# YuriPre.net
KiCad netlist of a schematic drawn in EasyEDA Pro
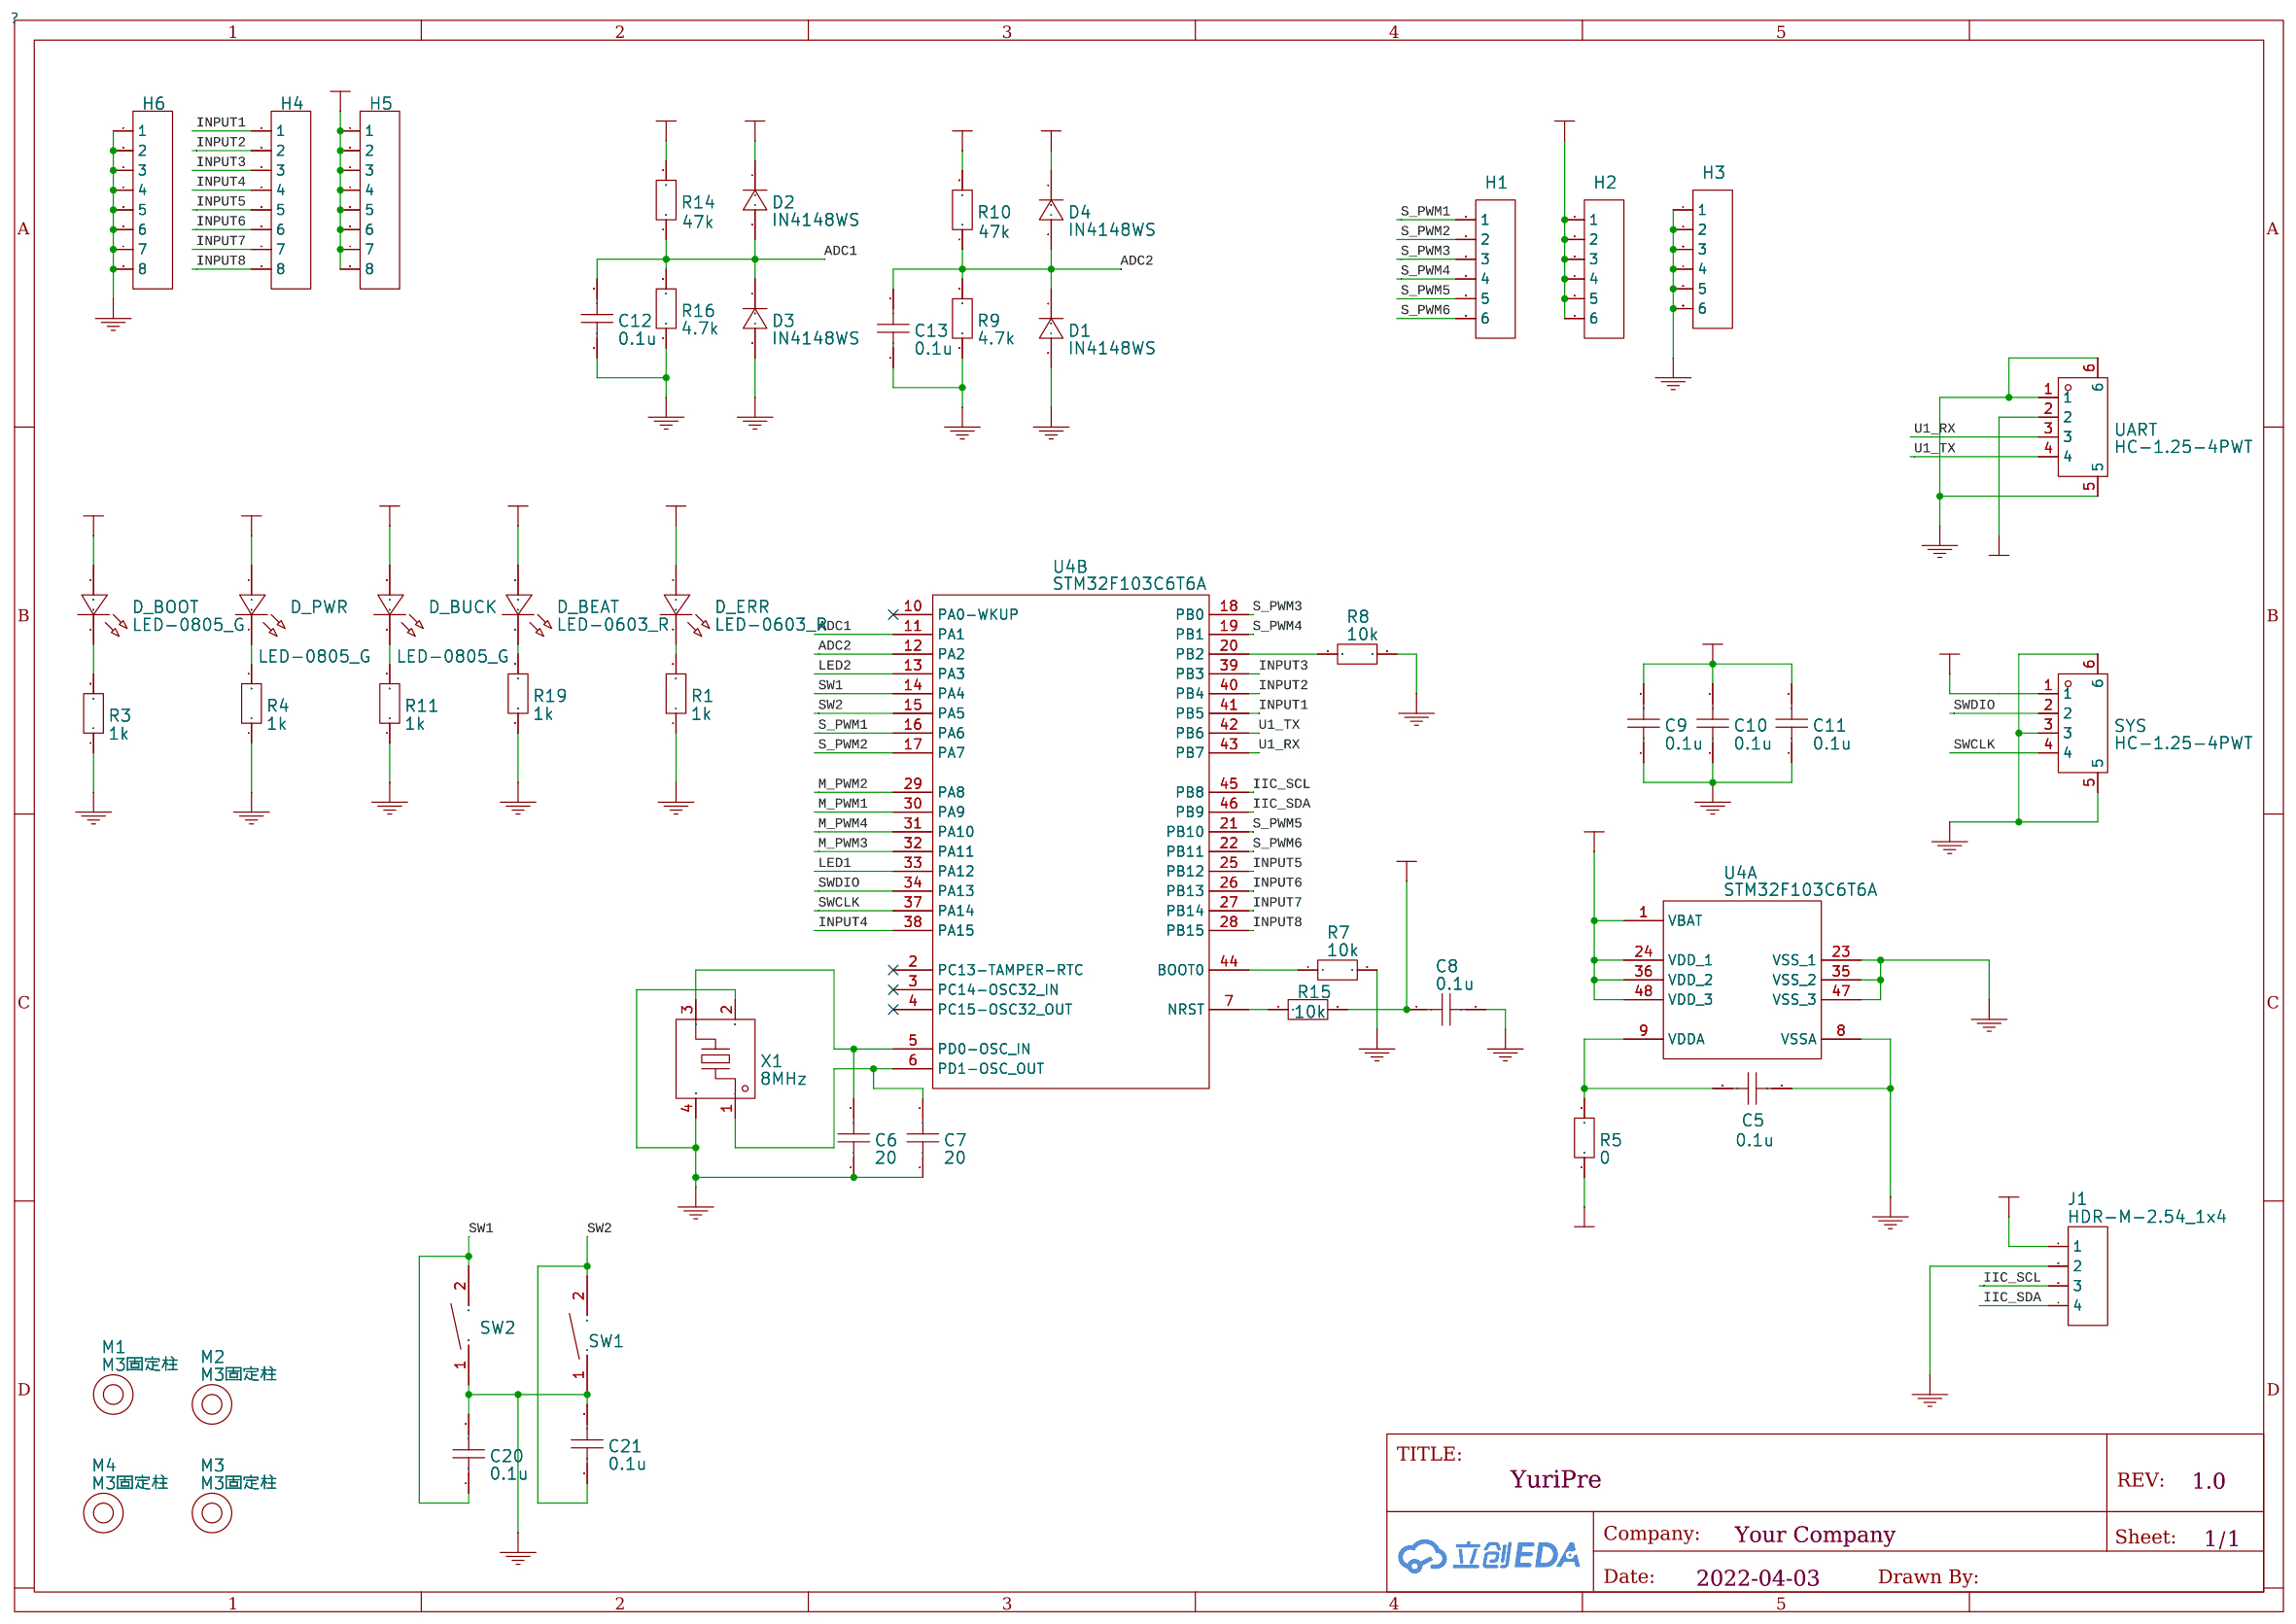
[diagram p0: MAIN_PART]
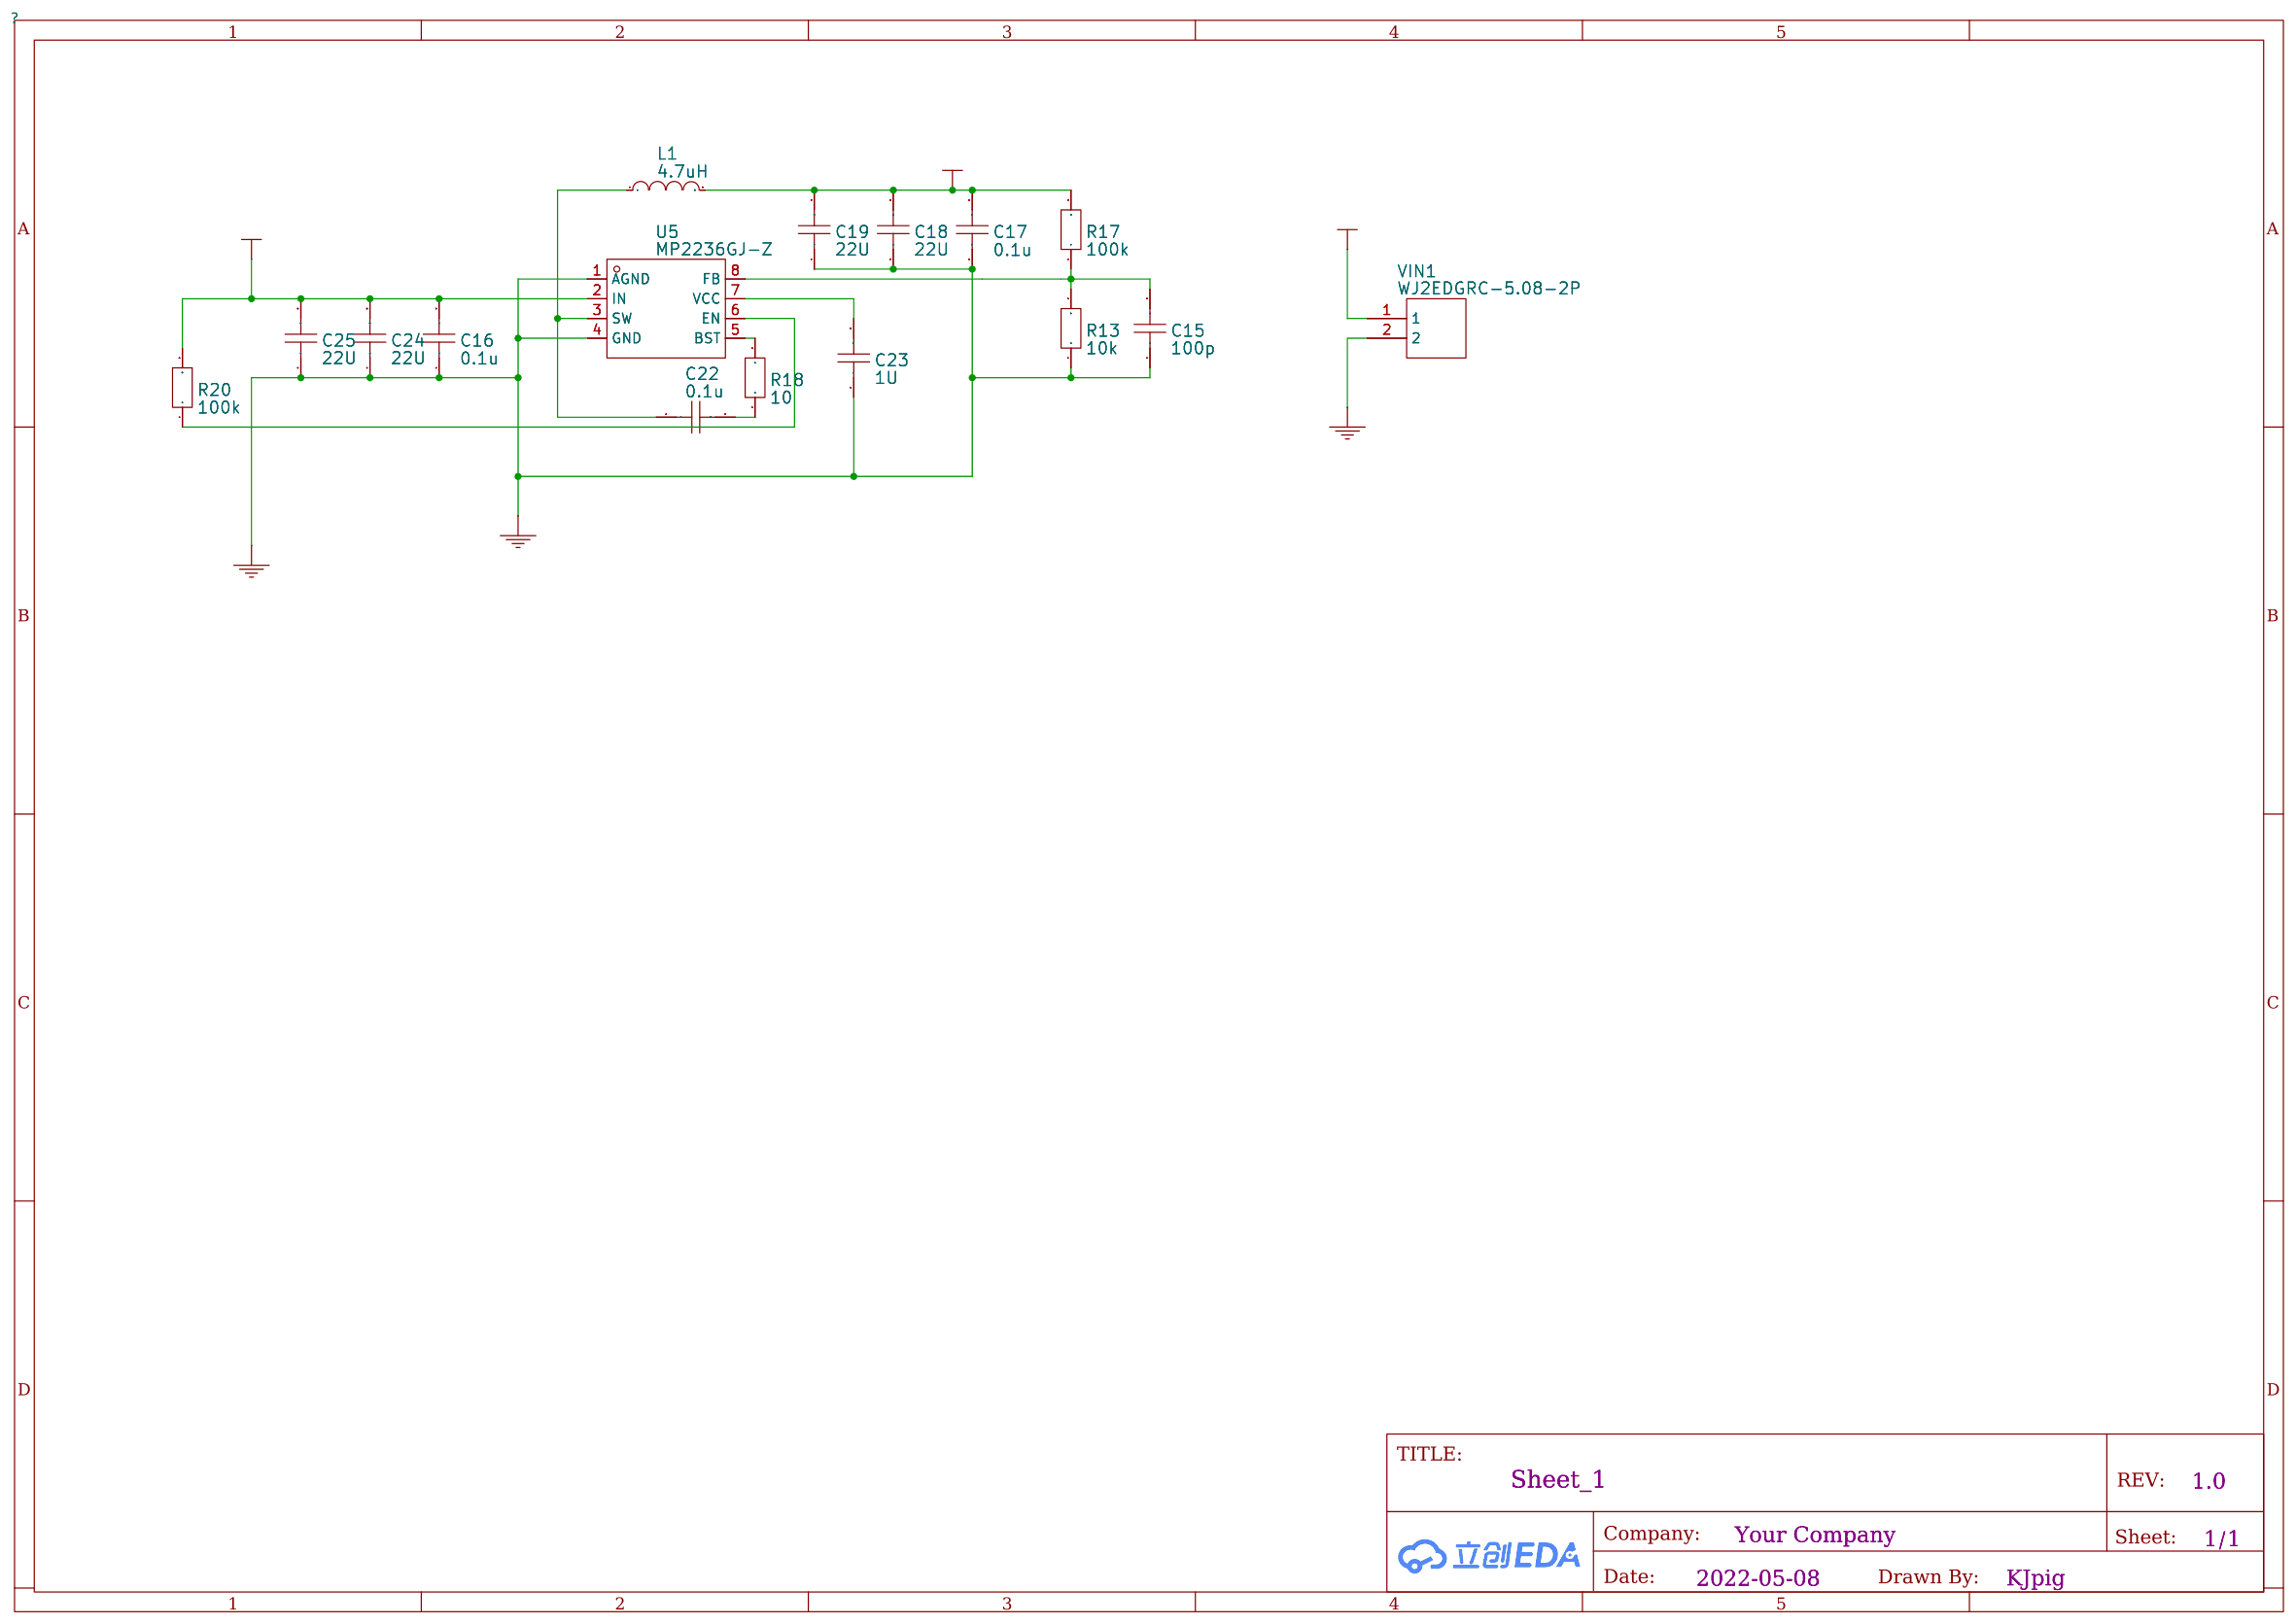
[diagram p1: PWR_PART]
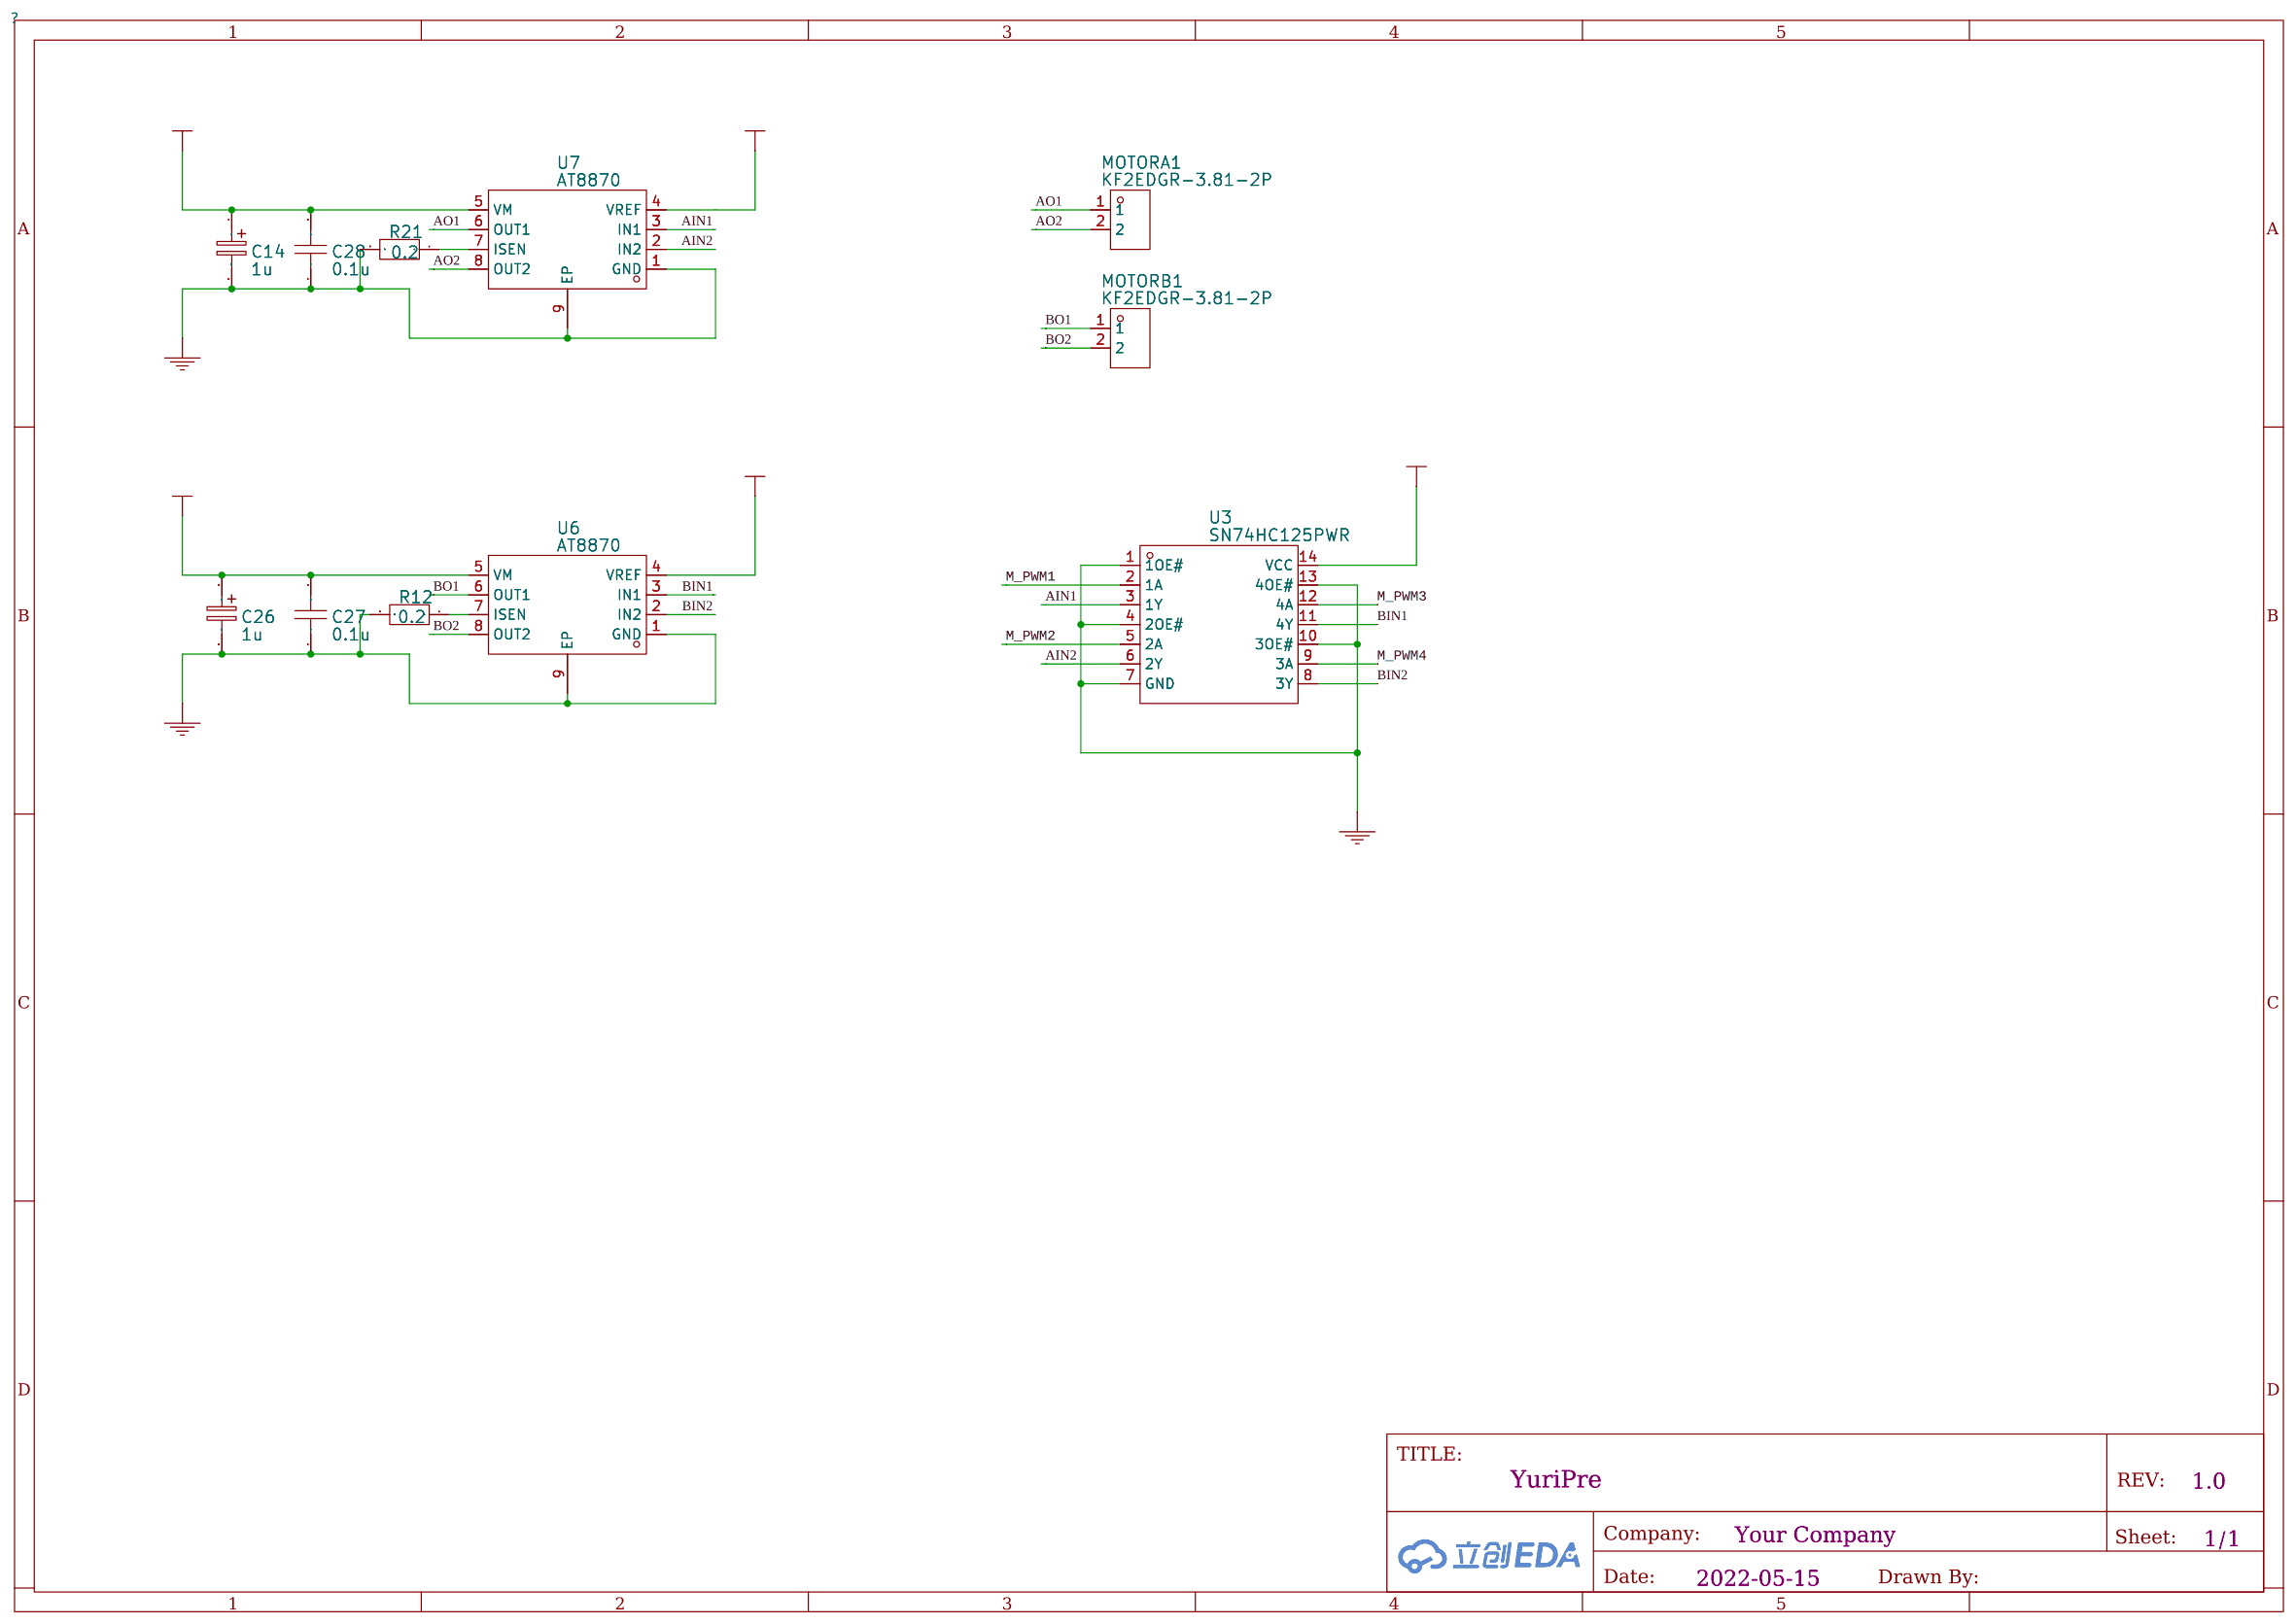
[diagram p2: MOTOR_PART]

(export (version "E")
  (design (tool "Eeschema 10.0.6"))
  (components
    (comp (ref "C5")
      (value "0.1u")
      (footprint "easyedapro:C0603")
      (libsource (lib "easyedapro") (part "0.1u"))
    )
    (comp (ref "C6") (value "20") (footprint "easyedapro:C0603") (libsource (lib "easyedapro") (part "20")))
    (comp (ref "C7") (value "20") (footprint "easyedapro:C0603") (libsource (lib "easyedapro") (part "20")))
    (comp (ref "C8")
      (value "0.1u")
      (footprint "easyedapro:C0603")
      (libsource (lib "easyedapro") (part "0.1u"))
    )
    (comp (ref "C9")
      (value "0.1u")
      (footprint "easyedapro:C0603")
      (libsource (lib "easyedapro") (part "0.1u"))
    )
    (comp (ref "C10")
      (value "0.1u")
      (footprint "easyedapro:C0603")
      (libsource (lib "easyedapro") (part "0.1u"))
    )
    (comp (ref "C11")
      (value "0.1u")
      (footprint "easyedapro:C0603")
      (libsource (lib "easyedapro") (part "0.1u"))
    )
    (comp (ref "C12")
      (value "0.1u")
      (footprint "easyedapro:C0603")
      (libsource (lib "easyedapro") (part "0.1u"))
    )
    (comp (ref "C13")
      (value "0.1u")
      (footprint "easyedapro:C0603")
      (libsource (lib "easyedapro") (part "0.1u"))
    )
    (comp (ref "C20")
      (value "0.1u")
      (footprint "easyedapro:C0603")
      (libsource (lib "easyedapro") (part "0.1u"))
    )
    (comp (ref "C21")
      (value "0.1u")
      (footprint "easyedapro:C0603")
      (libsource (lib "easyedapro") (part "0.1u"))
    )
    (comp (ref "D1")
      (value "IN4148WS")
      (footprint "easyedapro:SOD-323_L1.8-W1.3-LS2.5-RD")
      (fields (field (name "Manufacturer") "Leshan Radio"))
      (libsource (lib "easyedapro") (part "IN4148WS"))
    )
    (comp (ref "D2")
      (value "IN4148WS")
      (footprint "easyedapro:SOD-323_L1.8-W1.3-LS2.5-RD")
      (fields (field (name "Manufacturer") "Leshan Radio"))
      (libsource (lib "easyedapro") (part "IN4148WS"))
    )
    (comp (ref "D3")
      (value "IN4148WS")
      (footprint "easyedapro:SOD-323_L1.8-W1.3-LS2.5-RD")
      (fields (field (name "Manufacturer") "Leshan Radio"))
      (libsource (lib "easyedapro") (part "IN4148WS"))
    )
    (comp (ref "D4")
      (value "IN4148WS")
      (footprint "easyedapro:SOD-323_L1.8-W1.3-LS2.5-RD")
      (fields (field (name "Manufacturer") "Leshan Radio"))
      (libsource (lib "easyedapro") (part "IN4148WS"))
    )
    (comp (ref "D_BEAT")
      (value "LED-0603_R")
      (footprint "easyedapro:LED0603_RED")
      (fields
        (field (name "Manufacturer Part") "19-217/R6C-AL1M2VY/3T")
        (field (name "Manufacturer") "EVERLIGHT(台湾亿光)")
      )
      (libsource (lib "easyedapro") (part "LED-0603_R"))
    )
    (comp (ref "D_BOOT")
      (value "LED-0805_G")
      (footprint "easyedapro:LED0805_GREEN")
      (fields (field (name "Manufacturer Part") "NCD0805G1") (field (name "Manufacturer") "国星光电"))
      (libsource (lib "easyedapro") (part "LED-0805_G"))
    )
    (comp (ref "D_BUCK")
      (value "LED-0805_G")
      (footprint "easyedapro:LED0805_GREEN")
      (fields (field (name "Manufacturer Part") "NCD0805G1") (field (name "Manufacturer") "国星光电"))
      (libsource (lib "easyedapro") (part "LED-0805_G"))
    )
    (comp (ref "D_ERR")
      (value "LED-0603_R")
      (footprint "easyedapro:LED0603_RED")
      (fields
        (field (name "Manufacturer Part") "19-217/R6C-AL1M2VY/3T")
        (field (name "Manufacturer") "EVERLIGHT(台湾亿光)")
      )
      (libsource (lib "easyedapro") (part "LED-0603_R"))
    )
    (comp (ref "D_PWR")
      (value "LED-0805_G")
      (footprint "easyedapro:LED0805_GREEN")
      (fields (field (name "Manufacturer Part") "NCD0805G1") (field (name "Manufacturer") "国星光电"))
      (libsource (lib "easyedapro") (part "LED-0805_G"))
    )
    (comp (ref "H1")
      (value "HDR-F-2.54_1x6")
      (footprint "easyedapro:HDR-F-2.54_1X6")
      (libsource (lib "easyedapro") (part "HDR-F-2.54_1x6"))
    )
    (comp (ref "H2")
      (value "HDR-F-2.54_1x6")
      (footprint "easyedapro:HDR-F-2.54_1X6")
      (libsource (lib "easyedapro") (part "HDR-F-2.54_1x6"))
    )
    (comp (ref "H3")
      (value "HDR-F-2.54_1x6")
      (footprint "easyedapro:HDR-F-2.54_1X6")
      (libsource (lib "easyedapro") (part "HDR-F-2.54_1x6"))
    )
    (comp (ref "H4")
      (value "HDR-F-2.54_1x8")
      (footprint "easyedapro:HDR-F-2.54_1X8")
      (libsource (lib "easyedapro") (part "HDR-F-2.54_1x8"))
    )
    (comp (ref "H5")
      (value "HDR-F-2.54_1x8")
      (footprint "easyedapro:HDR-F-2.54_1X8")
      (libsource (lib "easyedapro") (part "HDR-F-2.54_1x8"))
    )
    (comp (ref "H6")
      (value "HDR-F-2.54_1x8")
      (footprint "easyedapro:HDR-F-2.54_1X8")
      (libsource (lib "easyedapro") (part "HDR-F-2.54_1x8"))
    )
    (comp (ref "J1")
      (value "HDR-M-2.54_1x4")
      (footprint "easyedapro:HDR-M-2.54_1X4")
      (libsource (lib "easyedapro") (part "HDR-M-2.54_1x4"))
    )
    (comp (ref "M1")
      (value "M3固定柱")
      (footprint "easyedapro:M3螺丝孔外直径6MM-带8小孔")
      (libsource (lib "easyedapro") (part "M3固定柱"))
    )
    (comp (ref "M2")
      (value "M3固定柱")
      (footprint "easyedapro:M3螺丝孔外直径6MM-带8小孔")
      (libsource (lib "easyedapro") (part "M3固定柱"))
    )
    (comp (ref "M3")
      (value "M3固定柱")
      (footprint "easyedapro:M3螺丝孔外直径6MM-带8小孔")
      (libsource (lib "easyedapro") (part "M3固定柱"))
    )
    (comp (ref "M4")
      (value "M3固定柱")
      (footprint "easyedapro:M3螺丝孔外直径6MM-带8小孔")
      (libsource (lib "easyedapro") (part "M3固定柱"))
    )
    (comp (ref "R1") (value "1k") (footprint "easyedapro:R0603") (libsource (lib "easyedapro") (part "1k")))
    (comp (ref "R3") (value "1k") (footprint "easyedapro:R0603") (libsource (lib "easyedapro") (part "1k")))
    (comp (ref "R4") (value "1k") (footprint "easyedapro:R0603") (libsource (lib "easyedapro") (part "1k")))
    (comp (ref "R5") (value "0") (footprint "easyedapro:R0603") (libsource (lib "easyedapro") (part "0_")))
    (comp (ref "R7") (value "10k") (footprint "easyedapro:R0603") (libsource (lib "easyedapro") (part "10k")))
    (comp (ref "R8") (value "10k") (footprint "easyedapro:R0603") (libsource (lib "easyedapro") (part "10k")))
    (comp (ref "R9")
      (value "4.7k")
      (footprint "easyedapro:R0603")
      (libsource (lib "easyedapro") (part "4.7k"))
    )
    (comp (ref "R10")
      (value "47k")
      (footprint "easyedapro:R0603")
      (libsource (lib "easyedapro") (part "47k"))
    )
    (comp (ref "R11") (value "1k") (footprint "easyedapro:R0603") (libsource (lib "easyedapro") (part "1k")))
    (comp (ref "R14")
      (value "47k")
      (footprint "easyedapro:R0603")
      (libsource (lib "easyedapro") (part "47k"))
    )
    (comp (ref "R15")
      (value "10k")
      (footprint "easyedapro:R0603")
      (libsource (lib "easyedapro") (part "10k"))
    )
    (comp (ref "R16")
      (value "4.7k")
      (footprint "easyedapro:R0603")
      (libsource (lib "easyedapro") (part "4.7k"))
    )
    (comp (ref "R19") (value "1k") (footprint "easyedapro:R0603") (libsource (lib "easyedapro") (part "1k")))
    (comp (ref "SW1")
      (value "TSA343G00D-250J2")
      (footprint "easyedapro:SW-SMD_L4.0-W2.9-P4.15-EH")
      (fields (field (name "Manufacturer") "BRIGHT"))
      (libsource (lib "easyedapro") (part "TSA343G00D-250J2"))
    )
    (comp (ref "SW2")
      (value "TSA343G00D-250J2")
      (footprint "easyedapro:SW-SMD_L4.0-W2.9-P4.15-EH")
      (fields (field (name "Manufacturer") "BRIGHT"))
      (libsource (lib "easyedapro") (part "TSA343G00D-250J2"))
    )
    (comp (ref "SYS")
      (value "HC-1.25-4PWT")
      (footprint "easyedapro:CONN-SMD_4P-P1.25-HC-1.25-4PWT")
      (fields (field (name "Manufacturer") "HCTL(华灿天禄)"))
      (libsource (lib "easyedapro") (part "HC-1.25-4PWT"))
    )
    (comp (ref "U4")
      (value "STM32F103C6T6A")
      (footprint "easyedapro:LQFP-48_L7.0-W7.0-P0.50-LS9.0-BL")
      (fields (field (name "Manufacturer") "ST"))
      (libsource (lib "easyedapro") (part "STM32F103C6T6A"))
    )
    (comp (ref "UART")
      (value "HC-1.25-4PWT")
      (footprint "easyedapro:CONN-SMD_4P-P1.25-HC-1.25-4PWT")
      (fields (field (name "Manufacturer") "HCTL(华灿天禄)"))
      (libsource (lib "easyedapro") (part "HC-1.25-4PWT"))
    )
    (comp (ref "X1")
      (value "8MHz")
      (footprint "easyedapro:CRYSTAL-SMD_4P-L3.2-W2.5-BL")
      (fields (field (name "Manufacturer Part") "X32258MSB4SI") (field (name "Manufacturer") "YXC扬兴科技"))
      (libsource (lib "easyedapro") (part "8MHz"))
    )
    (comp (ref "C15")
      (value "100p")
      (footprint "easyedapro:C0603")
      (libsource (lib "easyedapro") (part "100p"))
    )
    (comp (ref "C16")
      (value "0.1u")
      (footprint "easyedapro:C0603")
      (libsource (lib "easyedapro") (part "0.1u"))
    )
    (comp (ref "C17")
      (value "0.1u")
      (footprint "easyedapro:C0603")
      (libsource (lib "easyedapro") (part "0.1u"))
    )
    (comp (ref "C18")
      (value "22U")
      (footprint "easyedapro:C0805")
      (libsource (lib "easyedapro") (part "22U"))
    )
    (comp (ref "C19")
      (value "22U")
      (footprint "easyedapro:C0805")
      (libsource (lib "easyedapro") (part "22U"))
    )
    (comp (ref "C22")
      (value "0.1u")
      (footprint "easyedapro:C0603")
      (libsource (lib "easyedapro") (part "0.1u"))
    )
    (comp (ref "C23") (value "1U") (footprint "easyedapro:C0603") (libsource (lib "easyedapro") (part "1U")))
    (comp (ref "C24")
      (value "22U")
      (footprint "easyedapro:C0805")
      (libsource (lib "easyedapro") (part "22U"))
    )
    (comp (ref "C25")
      (value "22U")
      (footprint "easyedapro:C0805")
      (libsource (lib "easyedapro") (part "22U"))
    )
    (comp (ref "L1")
      (value "4.7uH")
      (footprint "easyedapro:IND-SMD_L7.1-W6.5")
      (fields (field (name "Manufacturer Part") "SPM6530T-4R7M") (field (name "Manufacturer") "TDK"))
      (libsource (lib "easyedapro") (part "4.7uH"))
    )
    (comp (ref "R13")
      (value "10k")
      (footprint "easyedapro:R0603")
      (libsource (lib "easyedapro") (part "10k"))
    )
    (comp (ref "R17")
      (value "100k")
      (footprint "easyedapro:R0603")
      (libsource (lib "easyedapro") (part "100k"))
    )
    (comp (ref "R18") (value "10") (footprint "easyedapro:R0603") (libsource (lib "easyedapro") (part "10")))
    (comp (ref "R20")
      (value "100k")
      (footprint "easyedapro:R0603")
      (libsource (lib "easyedapro") (part "100k"))
    )
    (comp (ref "U5")
      (value "MP2236GJ-Z")
      (footprint "easyedapro:TSOT-23-8_L2.9-W1.6-P0.65-LS2.8-BL")
      (libsource (lib "easyedapro") (part "MP2236GJ-Z"))
    )
    (comp (ref "VIN1")
      (value "WJ2EDGRC-5.08-2P")
      (footprint "easyedapro:CONN-TH_2P-P5.08_WJ2EDGRC-5.08-2P")
      (fields (field (name "Manufacturer") "ReliaPro"))
      (libsource (lib "easyedapro") (part "WJ2EDGRC-5.08-2P"))
    )
    (comp (ref "C14")
      (value "1u")
      (footprint "easyedapro:CAP-D6.3×H5.5")
      (libsource (lib "easyedapro") (part "1u"))
    )
    (comp (ref "C26")
      (value "1u")
      (footprint "easyedapro:CAP-D6.3×H5.5")
      (libsource (lib "easyedapro") (part "1u"))
    )
    (comp (ref "C27")
      (value "0.1u")
      (footprint "easyedapro:C0603")
      (libsource (lib "easyedapro") (part "0.1u"))
    )
    (comp (ref "C28")
      (value "0.1u")
      (footprint "easyedapro:C0603")
      (libsource (lib "easyedapro") (part "0.1u"))
    )
    (comp (ref "MOTORA1")
      (value "KF2EDGR-3.81-2P")
      (footprint "easyedapro:CONN-TH_2P-P3.81_KF2EDGR-3.81-2P")
      (fields (field (name "Manufacturer") "Cixi Kefa Elec"))
      (libsource (lib "easyedapro") (part "KF2EDGR-3.81-2P"))
    )
    (comp (ref "MOTORB1")
      (value "KF2EDGR-3.81-2P")
      (footprint "easyedapro:CONN-TH_2P-P3.81_KF2EDGR-3.81-2P")
      (fields (field (name "Manufacturer") "Cixi Kefa Elec"))
      (libsource (lib "easyedapro") (part "KF2EDGR-3.81-2P"))
    )
    (comp (ref "R12")
      (value "0.2")
      (footprint "easyedapro:R0603")
      (libsource (lib "easyedapro") (part "0.2"))
    )
    (comp (ref "R21")
      (value "0.2")
      (footprint "easyedapro:R0603")
      (libsource (lib "easyedapro") (part "0.2"))
    )
    (comp (ref "U3")
      (value "SN74HC125PWR")
      (footprint "easyedapro:TSSOP-14_L5.0-W4.4-P0.65-LS6.5-BL")
      (fields (field (name "Manufacturer") "Texas Instruments"))
      (libsource (lib "easyedapro") (part "SN74HC125PWR"))
    )
    (comp (ref "U6")
      (value "AT8870")
      (footprint "easyedapro:SOP-8_L4.9-W3.9-P1.27-LS6.0-BL-EP")
      (fields (field (name "Manufacturer") "Jiaxing Heroic Elec Tech"))
      (libsource (lib "easyedapro") (part "AT8870"))
    )
    (comp (ref "U7")
      (value "AT8870")
      (footprint "easyedapro:SOP-8_L4.9-W3.9-P1.27-LS6.0-BL-EP")
      (fields (field (name "Manufacturer") "Jiaxing Heroic Elec Tech"))
      (libsource (lib "easyedapro") (part "AT8870"))
    )
  )
  (nets
    (net (code "1") (name "+6.8V") (class "Default")
      (node (ref "C17") (pin "2") (pinfunction "2_2") (pintype "input"))
      (node (ref "C18") (pin "2") (pinfunction "2_2") (pintype "input"))
      (node (ref "C19") (pin "2") (pinfunction "2_2") (pintype "input"))
      (node (ref "D_BUCK") (pin "1") (pinfunction "1_1") (pintype "input"))
      (node (ref "H2") (pin "1") (pinfunction "1_1") (pintype "input"))
      (node (ref "H2") (pin "2") (pinfunction "2_2") (pintype "input"))
      (node (ref "H2") (pin "3") (pinfunction "3_3") (pintype "input"))
      (node (ref "H2") (pin "4") (pinfunction "4_4") (pintype "input"))
      (node (ref "H2") (pin "5") (pinfunction "5_5") (pintype "input"))
      (node (ref "H2") (pin "6") (pinfunction "6_6") (pintype "input"))
      (node (ref "L1") (pin "2") (pinfunction "2_2") (pintype "input"))
      (node (ref "R10") (pin "2") (pinfunction "2_2") (pintype "input"))
      (node (ref "R17") (pin "2") (pinfunction "2_2") (pintype "input"))
    )
    (net (code "2") (name "3V3") (class "Default")
      (node (ref "C10") (pin "2") (pinfunction "2_2") (pintype "input"))
      (node (ref "C11") (pin "2") (pinfunction "2_2") (pintype "input"))
      (node (ref "C8") (pin "1") (pinfunction "1_1") (pintype "input"))
      (node (ref "C9") (pin "2") (pinfunction "2_2") (pintype "input"))
      (node (ref "D2") (pin "1") (pinfunction "C_1") (pintype "input"))
      (node (ref "D4") (pin "1") (pinfunction "C_1") (pintype "input"))
      (node (ref "D_BEAT") (pin "1") (pinfunction "1_1") (pintype "input"))
      (node (ref "D_BOOT") (pin "1") (pinfunction "1_1") (pintype "input"))
      (node (ref "D_ERR") (pin "1") (pinfunction "1_1") (pintype "input"))
      (node (ref "H5") (pin "1") (pinfunction "1_1") (pintype "input"))
      (node (ref "H5") (pin "2") (pinfunction "2_2") (pintype "input"))
      (node (ref "H5") (pin "3") (pinfunction "3_3") (pintype "input"))
      (node (ref "H5") (pin "4") (pinfunction "4_4") (pintype "input"))
      (node (ref "H5") (pin "5") (pinfunction "5_5") (pintype "input"))
      (node (ref "H5") (pin "6") (pinfunction "6_6") (pintype "input"))
      (node (ref "H5") (pin "7") (pinfunction "7_7") (pintype "input"))
      (node (ref "H5") (pin "8") (pinfunction "8_8") (pintype "input"))
      (node (ref "J1") (pin "1") (pinfunction "1_1") (pintype "input"))
      (node (ref "R15") (pin "2") (pinfunction "2_2") (pintype "input"))
      (node (ref "R5") (pin "1") (pinfunction "1_1") (pintype "input"))
      (node (ref "SYS") (pin "1") (pinfunction "1_1") (pintype "input"))
      (node (ref "U3") (pin "14") (pinfunction "VCC_14") (pintype "input"))
      (node (ref "U4") (pin "1") (pinfunction "VBAT_1") (pintype "input"))
      (node (ref "U4") (pin "24") (pinfunction "VDD_1_24") (pintype "input"))
      (node (ref "U4") (pin "36") (pinfunction "VDD_2_36") (pintype "input"))
      (node (ref "U4") (pin "48") (pinfunction "VDD_3_48") (pintype "input"))
      (node (ref "U6") (pin "4") (pinfunction "VREF_4") (pintype "input"))
      (node (ref "U7") (pin "4") (pinfunction "VREF_4") (pintype "input"))
      (node (ref "UART") (pin "2") (pinfunction "2_2") (pintype "input"))
    )
    (net (code "3") (name "ADC1") (class "Default")
      (node (ref "C12") (pin "2") (pinfunction "2_2") (pintype "input"))
      (node (ref "D2") (pin "2") (pinfunction "A_2") (pintype "input"))
      (node (ref "D3") (pin "1") (pinfunction "C_1") (pintype "input"))
      (node (ref "R14") (pin "1") (pinfunction "1_1") (pintype "input"))
      (node (ref "R16") (pin "2") (pinfunction "2_2") (pintype "input"))
      (node (ref "U4") (pin "11") (pinfunction "PA1_11") (pintype "bidirectional"))
    )
    (net (code "4") (name "ADC2") (class "Default")
      (node (ref "C13") (pin "2") (pinfunction "2_2") (pintype "input"))
      (node (ref "D1") (pin "1") (pinfunction "C_1") (pintype "input"))
      (node (ref "D4") (pin "2") (pinfunction "A_2") (pintype "input"))
      (node (ref "R10") (pin "1") (pinfunction "1_1") (pintype "input"))
      (node (ref "R9") (pin "2") (pinfunction "2_2") (pintype "input"))
      (node (ref "U4") (pin "12") (pinfunction "PA2_12") (pintype "bidirectional"))
    )
    (net (code "5") (name "AIN1") (class "Default")
      (node (ref "U3") (pin "3") (pinfunction "1Y_3") (pintype "input"))
      (node (ref "U7") (pin "3") (pinfunction "IN1_3") (pintype "input"))
    )
    (net (code "6") (name "AIN2") (class "Default")
      (node (ref "U3") (pin "6") (pinfunction "2Y_6") (pintype "input"))
      (node (ref "U7") (pin "2") (pinfunction "IN2_2") (pintype "input"))
    )
    (net (code "7") (name "AO1") (class "Default")
      (node (ref "MOTORA1") (pin "1") (pinfunction "1_1") (pintype "input"))
      (node (ref "U7") (pin "6") (pinfunction "OUT1_6") (pintype "input"))
    )
    (net (code "8") (name "AO2") (class "Default")
      (node (ref "MOTORA1") (pin "2") (pinfunction "2_2") (pintype "input"))
      (node (ref "U7") (pin "8") (pinfunction "OUT2_8") (pintype "input"))
    )
    (net (code "9") (name "BIN1") (class "Default")
      (node (ref "U3") (pin "11") (pinfunction "4Y_11") (pintype "input"))
      (node (ref "U6") (pin "3") (pinfunction "IN1_3") (pintype "input"))
    )
    (net (code "10") (name "BIN2") (class "Default")
      (node (ref "U3") (pin "8") (pinfunction "3Y_8") (pintype "input"))
      (node (ref "U6") (pin "2") (pinfunction "IN2_2") (pintype "input"))
    )
    (net (code "11") (name "BO1") (class "Default")
      (node (ref "MOTORB1") (pin "1") (pinfunction "1_1") (pintype "input"))
      (node (ref "U6") (pin "6") (pinfunction "OUT1_6") (pintype "input"))
    )
    (net (code "12") (name "BO2") (class "Default")
      (node (ref "MOTORB1") (pin "2") (pinfunction "2_2") (pintype "input"))
      (node (ref "U6") (pin "8") (pinfunction "OUT2_8") (pintype "input"))
    )
    (net (code "13") (name "GND") (class "Default")
      (node (ref "C10") (pin "1") (pinfunction "1_1") (pintype "input"))
      (node (ref "C11") (pin "1") (pinfunction "1_1") (pintype "input"))
      (node (ref "C12") (pin "1") (pinfunction "1_1") (pintype "input"))
      (node (ref "C13") (pin "1") (pinfunction "1_1") (pintype "input"))
      (node (ref "C14") (pin "2") (pinfunction "2_2") (pintype "input"))
      (node (ref "C15") (pin "1") (pinfunction "1_1") (pintype "input"))
      (node (ref "C16") (pin "1") (pinfunction "1_1") (pintype "input"))
      (node (ref "C17") (pin "1") (pinfunction "1_1") (pintype "input"))
      (node (ref "C18") (pin "1") (pinfunction "1_1") (pintype "input"))
      (node (ref "C19") (pin "1") (pinfunction "1_1") (pintype "input"))
      (node (ref "C20") (pin "2") (pinfunction "2_2") (pintype "input"))
      (node (ref "C21") (pin "2") (pinfunction "2_2") (pintype "input"))
      (node (ref "C23") (pin "1") (pinfunction "1_1") (pintype "input"))
      (node (ref "C24") (pin "1") (pinfunction "1_1") (pintype "input"))
      (node (ref "C25") (pin "1") (pinfunction "1_1") (pintype "input"))
      (node (ref "C26") (pin "2") (pinfunction "2_2") (pintype "input"))
      (node (ref "C27") (pin "1") (pinfunction "1_1") (pintype "input"))
      (node (ref "C28") (pin "1") (pinfunction "1_1") (pintype "input"))
      (node (ref "C5") (pin "2") (pinfunction "2_2") (pintype "input"))
      (node (ref "C6") (pin "1") (pinfunction "1_1") (pintype "input"))
      (node (ref "C7") (pin "1") (pinfunction "1_1") (pintype "input"))
      (node (ref "C8") (pin "2") (pinfunction "2_2") (pintype "input"))
      (node (ref "C9") (pin "1") (pinfunction "1_1") (pintype "input"))
      (node (ref "D1") (pin "2") (pinfunction "A_2") (pintype "input"))
      (node (ref "D3") (pin "2") (pinfunction "A_2") (pintype "input"))
      (node (ref "H3") (pin "1") (pinfunction "1_1") (pintype "input"))
      (node (ref "H3") (pin "2") (pinfunction "2_2") (pintype "input"))
      (node (ref "H3") (pin "3") (pinfunction "3_3") (pintype "input"))
      (node (ref "H3") (pin "4") (pinfunction "4_4") (pintype "input"))
      (node (ref "H3") (pin "5") (pinfunction "5_5") (pintype "input"))
      (node (ref "H3") (pin "6") (pinfunction "6_6") (pintype "input"))
      (node (ref "H6") (pin "1") (pinfunction "1_1") (pintype "input"))
      (node (ref "H6") (pin "2") (pinfunction "2_2") (pintype "input"))
      (node (ref "H6") (pin "3") (pinfunction "3_3") (pintype "input"))
      (node (ref "H6") (pin "4") (pinfunction "4_4") (pintype "input"))
      (node (ref "H6") (pin "5") (pinfunction "5_5") (pintype "input"))
      (node (ref "H6") (pin "6") (pinfunction "6_6") (pintype "input"))
      (node (ref "H6") (pin "7") (pinfunction "7_7") (pintype "input"))
      (node (ref "H6") (pin "8") (pinfunction "8_8") (pintype "input"))
      (node (ref "J1") (pin "2") (pinfunction "2_2") (pintype "input"))
      (node (ref "R11") (pin "1") (pinfunction "1_1") (pintype "input"))
      (node (ref "R12") (pin "2") (pinfunction "2_2") (pintype "input"))
      (node (ref "R13") (pin "1") (pinfunction "1_1") (pintype "input"))
      (node (ref "R16") (pin "1") (pinfunction "1_1") (pintype "input"))
      (node (ref "R21") (pin "2") (pinfunction "2_2") (pintype "input"))
      (node (ref "R3") (pin "1") (pinfunction "1_1") (pintype "input"))
      (node (ref "R4") (pin "1") (pinfunction "1_1") (pintype "input"))
      (node (ref "R7") (pin "2") (pinfunction "2_2") (pintype "input"))
      (node (ref "R8") (pin "2") (pinfunction "2_2") (pintype "input"))
      (node (ref "R9") (pin "1") (pinfunction "1_1") (pintype "input"))
      (node (ref "SW1") (pin "1") (pinfunction "1_1") (pintype "input"))
      (node (ref "SW2") (pin "1") (pinfunction "1_1") (pintype "input"))
      (node (ref "SYS") (pin "3") (pinfunction "3_3") (pintype "input"))
      (node (ref "SYS") (pin "5") (pinfunction "5_5") (pintype "input"))
      (node (ref "SYS") (pin "6") (pinfunction "6_6") (pintype "input"))
      (node (ref "U3") (pin "1") (pinfunction "1OE#_1") (pintype "input"))
      (node (ref "U3") (pin "10") (pinfunction "3OE#_10") (pintype "input"))
      (node (ref "U3") (pin "13") (pinfunction "4OE#_13") (pintype "input"))
      (node (ref "U3") (pin "4") (pinfunction "2OE#_4") (pintype "input"))
      (node (ref "U3") (pin "7") (pinfunction "GND_7") (pintype "input"))
      (node (ref "U4") (pin "23") (pinfunction "VSS_1_23") (pintype "input"))
      (node (ref "U4") (pin "35") (pinfunction "VSS_2_35") (pintype "input"))
      (node (ref "U4") (pin "47") (pinfunction "VSS_3_47") (pintype "input"))
      (node (ref "U4") (pin "8") (pinfunction "VSSA_8") (pintype "input"))
      (node (ref "U5") (pin "1") (pinfunction "AGND_1") (pintype "input"))
      (node (ref "U5") (pin "4") (pinfunction "GND_4") (pintype "input"))
      (node (ref "U6") (pin "1") (pinfunction "GND_1") (pintype "input"))
      (node (ref "U6") (pin "9") (pinfunction "EP_9") (pintype "input"))
      (node (ref "U7") (pin "1") (pinfunction "GND_1") (pintype "input"))
      (node (ref "U7") (pin "9") (pinfunction "EP_9") (pintype "input"))
      (node (ref "UART") (pin "1") (pinfunction "1_1") (pintype "input"))
      (node (ref "UART") (pin "5") (pinfunction "5_5") (pintype "input"))
      (node (ref "UART") (pin "6") (pinfunction "6_6") (pintype "input"))
      (node (ref "VIN1") (pin "2") (pinfunction "2_2") (pintype "input"))
      (node (ref "X1") (pin "2") (pinfunction "GND_2") (pintype "input"))
      (node (ref "X1") (pin "4") (pinfunction "GND_4") (pintype "input"))
    )
    (net (code "14") (name "IIC_SCL") (class "Default")
      (node (ref "J1") (pin "3") (pinfunction "3_3") (pintype "input"))
      (node (ref "U4") (pin "45") (pinfunction "PB8_45") (pintype "bidirectional"))
    )
    (net (code "15") (name "IIC_SDA") (class "Default")
      (node (ref "J1") (pin "4") (pinfunction "4_4") (pintype "input"))
      (node (ref "U4") (pin "46") (pinfunction "PB9_46") (pintype "bidirectional"))
    )
    (net (code "16") (name "INPUT1") (class "Default")
      (node (ref "H4") (pin "1") (pinfunction "1_1") (pintype "input"))
      (node (ref "U4") (pin "41") (pinfunction "PB5_41") (pintype "bidirectional"))
    )
    (net (code "17") (name "INPUT2") (class "Default")
      (node (ref "H4") (pin "2") (pinfunction "2_2") (pintype "input"))
      (node (ref "U4") (pin "40") (pinfunction "PB4_40") (pintype "bidirectional"))
    )
    (net (code "18") (name "INPUT3") (class "Default")
      (node (ref "H4") (pin "3") (pinfunction "3_3") (pintype "input"))
      (node (ref "U4") (pin "39") (pinfunction "PB3_39") (pintype "bidirectional"))
    )
    (net (code "19") (name "INPUT4") (class "Default")
      (node (ref "H4") (pin "4") (pinfunction "4_4") (pintype "input"))
      (node (ref "U4") (pin "38") (pinfunction "PA15_38") (pintype "bidirectional"))
    )
    (net (code "20") (name "INPUT5") (class "Default")
      (node (ref "H4") (pin "5") (pinfunction "5_5") (pintype "input"))
      (node (ref "U4") (pin "25") (pinfunction "PB12_25") (pintype "bidirectional"))
    )
    (net (code "21") (name "INPUT6") (class "Default")
      (node (ref "H4") (pin "6") (pinfunction "6_6") (pintype "input"))
      (node (ref "U4") (pin "26") (pinfunction "PB13_26") (pintype "bidirectional"))
    )
    (net (code "22") (name "INPUT7") (class "Default")
      (node (ref "H4") (pin "7") (pinfunction "7_7") (pintype "input"))
      (node (ref "U4") (pin "27") (pinfunction "PB14_27") (pintype "bidirectional"))
    )
    (net (code "23") (name "INPUT8") (class "Default")
      (node (ref "H4") (pin "8") (pinfunction "8_8") (pintype "input"))
      (node (ref "U4") (pin "28") (pinfunction "PB15_28") (pintype "bidirectional"))
    )
    (net (code "24") (name "LED1") (class "Default")
      (node (ref "R19") (pin "1") (pinfunction "1_1") (pintype "input"))
      (node (ref "U4") (pin "33") (pinfunction "PA12_33") (pintype "bidirectional"))
    )
    (net (code "25") (name "LED2") (class "Default")
      (node (ref "R1") (pin "1") (pinfunction "1_1") (pintype "input"))
      (node (ref "U4") (pin "13") (pinfunction "PA3_13") (pintype "bidirectional"))
    )
    (net (code "26") (name "M_PWM1") (class "Default")
      (node (ref "U3") (pin "2") (pinfunction "1A_2") (pintype "input"))
      (node (ref "U4") (pin "30") (pinfunction "PA9_30") (pintype "bidirectional"))
    )
    (net (code "27") (name "M_PWM2") (class "Default")
      (node (ref "U3") (pin "5") (pinfunction "2A_5") (pintype "input"))
      (node (ref "U4") (pin "29") (pinfunction "PA8_29") (pintype "bidirectional"))
    )
    (net (code "28") (name "M_PWM3") (class "Default")
      (node (ref "U3") (pin "12") (pinfunction "4A_12") (pintype "input"))
      (node (ref "U4") (pin "32") (pinfunction "PA11_32") (pintype "bidirectional"))
    )
    (net (code "29") (name "M_PWM4") (class "Default")
      (node (ref "U3") (pin "9") (pinfunction "3A_9") (pintype "input"))
      (node (ref "U4") (pin "31") (pinfunction "PA10_31") (pintype "bidirectional"))
    )
    (net (code "30") (name "Net-(C22-Pad2)") (class "Default")
      (node (ref "C22") (pin "2") (pinfunction "2_2") (pintype "input"))
      (node (ref "R18") (pin "1") (pinfunction "1_1") (pintype "input"))
    )
    (net (code "31") (name "Net-(D_BEAT-Pad2)") (class "Default")
      (node (ref "D_BEAT") (pin "2") (pinfunction "2_2") (pintype "input"))
      (node (ref "R19") (pin "2") (pinfunction "2_2") (pintype "input"))
    )
    (net (code "32") (name "Net-(D_BOOT-Pad2)") (class "Default")
      (node (ref "D_BOOT") (pin "2") (pinfunction "2_2") (pintype "input"))
      (node (ref "R3") (pin "2") (pinfunction "2_2") (pintype "input"))
    )
    (net (code "33") (name "Net-(D_BUCK-Pad2)") (class "Default")
      (node (ref "D_BUCK") (pin "2") (pinfunction "2_2") (pintype "input"))
      (node (ref "R11") (pin "2") (pinfunction "2_2") (pintype "input"))
    )
    (net (code "34") (name "Net-(D_ERR-Pad2)") (class "Default")
      (node (ref "D_ERR") (pin "2") (pinfunction "2_2") (pintype "input"))
      (node (ref "R1") (pin "2") (pinfunction "2_2") (pintype "input"))
    )
    (net (code "35") (name "Net-(D_PWR-Pad2)") (class "Default")
      (node (ref "D_PWR") (pin "2") (pinfunction "2_2") (pintype "input"))
      (node (ref "R4") (pin "2") (pinfunction "2_2") (pintype "input"))
    )
    (net (code "36") (name "Net-(U4A-VDDA)") (class "Default")
      (node (ref "C5") (pin "1") (pinfunction "1_1") (pintype "input"))
      (node (ref "R5") (pin "2") (pinfunction "2_2") (pintype "input"))
      (node (ref "U4") (pin "9") (pinfunction "VDDA_9") (pintype "input"))
    )
    (net (code "37") (name "Net-(U4B-BOOT0)") (class "Default")
      (node (ref "R7") (pin "1") (pinfunction "1_1") (pintype "input"))
      (node (ref "U4") (pin "44") (pinfunction "BOOT0_44") (pintype "input"))
    )
    (net (code "38") (name "Net-(U4B-NRST)") (class "Default")
      (node (ref "R15") (pin "1") (pinfunction "1_1") (pintype "input"))
      (node (ref "U4") (pin "7") (pinfunction "NRST_7") (pintype "bidirectional"))
    )
    (net (code "39") (name "Net-(U4B-PB2)") (class "Default")
      (node (ref "R8") (pin "1") (pinfunction "1_1") (pintype "input"))
      (node (ref "U4") (pin "20") (pinfunction "PB2_20") (pintype "bidirectional"))
    )
    (net (code "40") (name "Net-(U4B-PD0-OSC_IN)") (class "Default")
      (node (ref "C6") (pin "2") (pinfunction "2_2") (pintype "input"))
      (node (ref "U4") (pin "5") (pinfunction "PD0-OSC_IN_5") (pintype "bidirectional"))
      (node (ref "X1") (pin "3") (pinfunction "3_3") (pintype "input"))
    )
    (net (code "41") (name "Net-(U4B-PD1-OSC_OUT)") (class "Default")
      (node (ref "C7") (pin "2") (pinfunction "2_2") (pintype "input"))
      (node (ref "U4") (pin "6") (pinfunction "PD1-OSC_OUT_6") (pintype "bidirectional"))
      (node (ref "X1") (pin "1") (pinfunction "1_1") (pintype "input"))
    )
    (net (code "42") (name "Net-(U5-BST)") (class "Default")
      (node (ref "R18") (pin "2") (pinfunction "2_2") (pintype "input"))
      (node (ref "U5") (pin "5") (pinfunction "BST_5") (pintype "input"))
    )
    (net (code "43") (name "Net-(U5-EN)") (class "Default")
      (node (ref "R20") (pin "1") (pinfunction "1_1") (pintype "input"))
      (node (ref "U5") (pin "6") (pinfunction "EN_6") (pintype "input"))
    )
    (net (code "44") (name "Net-(U5-FB)") (class "Default")
      (node (ref "C15") (pin "2") (pinfunction "2_2") (pintype "input"))
      (node (ref "R13") (pin "2") (pinfunction "2_2") (pintype "input"))
      (node (ref "R17") (pin "1") (pinfunction "1_1") (pintype "input"))
      (node (ref "U5") (pin "8") (pinfunction "FB_8") (pintype "input"))
    )
    (net (code "45") (name "Net-(U5-SW)") (class "Default")
      (node (ref "C22") (pin "1") (pinfunction "1_1") (pintype "input"))
      (node (ref "L1") (pin "1") (pinfunction "1_1") (pintype "input"))
      (node (ref "U5") (pin "3") (pinfunction "SW_3") (pintype "input"))
    )
    (net (code "46") (name "Net-(U5-VCC)") (class "Default")
      (node (ref "C23") (pin "2") (pinfunction "2_2") (pintype "input"))
      (node (ref "U5") (pin "7") (pinfunction "VCC_7") (pintype "input"))
    )
    (net (code "47") (name "Net-(U6-ISEN)") (class "Default")
      (node (ref "R12") (pin "1") (pinfunction "1_1") (pintype "input"))
      (node (ref "U6") (pin "7") (pinfunction "ISEN_7") (pintype "input"))
    )
    (net (code "48") (name "Net-(U7-ISEN)") (class "Default")
      (node (ref "R21") (pin "1") (pinfunction "1_1") (pintype "input"))
      (node (ref "U7") (pin "7") (pinfunction "ISEN_7") (pintype "input"))
    )
    (net (code "49") (name "SW1") (class "Default")
      (node (ref "C20") (pin "1") (pinfunction "1_1") (pintype "input"))
      (node (ref "SW2") (pin "2") (pinfunction "2_2") (pintype "input"))
      (node (ref "U4") (pin "14") (pinfunction "PA4_14") (pintype "bidirectional"))
    )
    (net (code "50") (name "SW2") (class "Default")
      (node (ref "C21") (pin "1") (pinfunction "1_1") (pintype "input"))
      (node (ref "SW1") (pin "2") (pinfunction "2_2") (pintype "input"))
      (node (ref "U4") (pin "15") (pinfunction "PA5_15") (pintype "bidirectional"))
    )
    (net (code "51") (name "SWCLK") (class "Default")
      (node (ref "SYS") (pin "4") (pinfunction "4_4") (pintype "input"))
      (node (ref "U4") (pin "37") (pinfunction "PA14_37") (pintype "bidirectional"))
    )
    (net (code "52") (name "SWDIO") (class "Default")
      (node (ref "SYS") (pin "2") (pinfunction "2_2") (pintype "input"))
      (node (ref "U4") (pin "34") (pinfunction "PA13_34") (pintype "bidirectional"))
    )
    (net (code "53") (name "S_PWM1") (class "Default")
      (node (ref "H1") (pin "1") (pinfunction "1_1") (pintype "input"))
      (node (ref "U4") (pin "16") (pinfunction "PA6_16") (pintype "bidirectional"))
    )
    (net (code "54") (name "S_PWM2") (class "Default")
      (node (ref "H1") (pin "2") (pinfunction "2_2") (pintype "input"))
      (node (ref "U4") (pin "17") (pinfunction "PA7_17") (pintype "bidirectional"))
    )
    (net (code "55") (name "S_PWM3") (class "Default")
      (node (ref "H1") (pin "3") (pinfunction "3_3") (pintype "input"))
      (node (ref "U4") (pin "18") (pinfunction "PB0_18") (pintype "bidirectional"))
    )
    (net (code "56") (name "S_PWM4") (class "Default")
      (node (ref "H1") (pin "4") (pinfunction "4_4") (pintype "input"))
      (node (ref "U4") (pin "19") (pinfunction "PB1_19") (pintype "bidirectional"))
    )
    (net (code "57") (name "S_PWM5") (class "Default")
      (node (ref "H1") (pin "5") (pinfunction "5_5") (pintype "input"))
      (node (ref "U4") (pin "21") (pinfunction "PB10_21") (pintype "bidirectional"))
    )
    (net (code "58") (name "S_PWM6") (class "Default")
      (node (ref "H1") (pin "6") (pinfunction "6_6") (pintype "input"))
      (node (ref "U4") (pin "22") (pinfunction "PB11_22") (pintype "bidirectional"))
    )
    (net (code "59") (name "U1_RX") (class "Default")
      (node (ref "U4") (pin "43") (pinfunction "PB7_43") (pintype "bidirectional"))
      (node (ref "UART") (pin "3") (pinfunction "3_3") (pintype "input"))
    )
    (net (code "60") (name "U1_TX") (class "Default")
      (node (ref "U4") (pin "42") (pinfunction "PB6_42") (pintype "bidirectional"))
      (node (ref "UART") (pin "4") (pinfunction "4_4") (pintype "input"))
    )
    (net (code "61") (name "VIN") (class "Default")
      (node (ref "C14") (pin "1") (pinfunction "1_1") (pintype "input"))
      (node (ref "C16") (pin "2") (pinfunction "2_2") (pintype "input"))
      (node (ref "C24") (pin "2") (pinfunction "2_2") (pintype "input"))
      (node (ref "C25") (pin "2") (pinfunction "2_2") (pintype "input"))
      (node (ref "C26") (pin "1") (pinfunction "1_1") (pintype "input"))
      (node (ref "C27") (pin "2") (pinfunction "2_2") (pintype "input"))
      (node (ref "C28") (pin "2") (pinfunction "2_2") (pintype "input"))
      (node (ref "D_PWR") (pin "1") (pinfunction "1_1") (pintype "input"))
      (node (ref "R14") (pin "2") (pinfunction "2_2") (pintype "input"))
      (node (ref "R20") (pin "2") (pinfunction "2_2") (pintype "input"))
      (node (ref "U5") (pin "2") (pinfunction "IN_2") (pintype "input"))
      (node (ref "U6") (pin "5") (pinfunction "VM_5") (pintype "input"))
      (node (ref "U7") (pin "5") (pinfunction "VM_5") (pintype "input"))
      (node (ref "VIN1") (pin "1") (pinfunction "1_1") (pintype "input"))
    )
    (net (code "62") (name "unconnected-(U4B-PA0-WKUP-Pad10)") (class "Default")
      (node (ref "U4") (pin "10") (pinfunction "PA0-WKUP_10") (pintype "bidirectional+no_connect"))
    )
    (net (code "63") (name "unconnected-(U4B-PC13-TAMPER-RTC-Pad2)") (class "Default")
      (node (ref "U4") (pin "2") (pinfunction "PC13-TAMPER-RTC_2") (pintype "bidirectional+no_connect"))
    )
    (net (code "64") (name "unconnected-(U4B-PC14-OSC32_IN-Pad3)") (class "Default")
      (node (ref "U4") (pin "3") (pinfunction "PC14-OSC32_IN_3") (pintype "bidirectional+no_connect"))
    )
    (net (code "65") (name "unconnected-(U4B-PC15-OSC32_OUT-Pad4)") (class "Default")
      (node (ref "U4") (pin "4") (pinfunction "PC15-OSC32_OUT_4") (pintype "bidirectional+no_connect"))
    )
  )
)
